# rgb.net
KiCad netlist of a schematic drawn in EAGLE
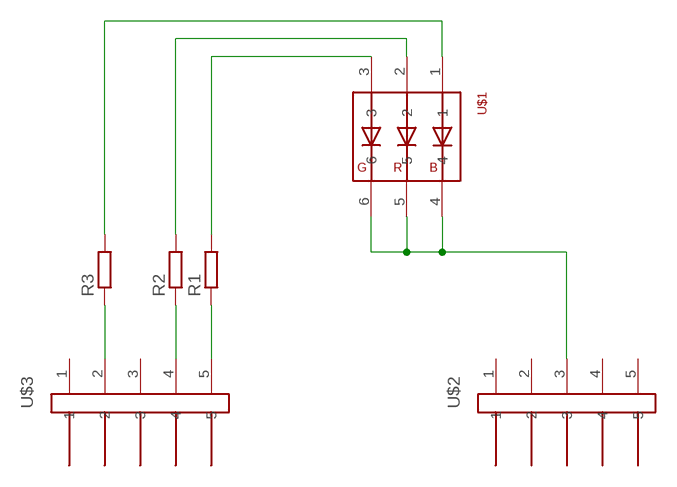
[diagram p0: schematic, sheet 1]

(export (version "E")
  (design (tool "Eeschema 10.0.6"))
  (components
    (comp (ref "R1")
      (value "R-EU_R0603")
      (footprint "eagle-import:R0603")
      (libsource (lib "eagle-import") (part "R-EU_R0603"))
    )
    (comp (ref "R2")
      (value "R-EU_R0603")
      (footprint "eagle-import:R0603")
      (libsource (lib "eagle-import") (part "R-EU_R0603"))
    )
    (comp (ref "R3")
      (value "R-EU_R0603")
      (footprint "eagle-import:R0603")
      (libsource (lib "eagle-import") (part "R-EU_R0603"))
    )
    (comp (ref "U$1")
      (value "RGB_WW-FCE50TC-Q1")
      (footprint "eagle-import:RGB_WW-FCE50TC-Q1")
      (libsource (lib "eagle-import") (part "RGB_WW-FCE50TC-Q1"))
    )
    (comp (ref "U$2")
      (value "JUMPER5M")
      (footprint "eagle-import:JUMPER5M")
      (libsource (lib "eagle-import") (part "JUMPER5M"))
    )
    (comp (ref "U$3")
      (value "JUMPER5M")
      (footprint "eagle-import:JUMPER5M")
      (libsource (lib "eagle-import") (part "JUMPER5M"))
    )
  )
  (nets
    (net (code "1") (name "Net-(R1-Pad1)") (class "Default")
      (node (ref "R1") (pin "1") (pinfunction "1_1") (pintype "passive"))
      (node (ref "U$3") (pin "5") (pinfunction "5_5") (pintype "bidirectional"))
    )
    (net (code "2") (name "Net-(R1-Pad2)") (class "Default")
      (node (ref "R1") (pin "2") (pinfunction "2_2") (pintype "passive"))
      (node (ref "U$1") (pin "3") (pinfunction "3_3") (pintype "bidirectional"))
    )
    (net (code "3") (name "Net-(R2-Pad1)") (class "Default")
      (node (ref "R2") (pin "1") (pinfunction "1_1") (pintype "passive"))
      (node (ref "U$3") (pin "4") (pinfunction "4_4") (pintype "bidirectional"))
    )
    (net (code "4") (name "Net-(R2-Pad2)") (class "Default")
      (node (ref "R2") (pin "2") (pinfunction "2_2") (pintype "passive"))
      (node (ref "U$1") (pin "2") (pinfunction "2_2") (pintype "bidirectional"))
    )
    (net (code "5") (name "Net-(R3-Pad1)") (class "Default")
      (node (ref "R3") (pin "1") (pinfunction "1_1") (pintype "passive"))
      (node (ref "U$3") (pin "2") (pinfunction "2_2") (pintype "bidirectional"))
    )
    (net (code "6") (name "Net-(R3-Pad2)") (class "Default")
      (node (ref "R3") (pin "2") (pinfunction "2_2") (pintype "passive"))
      (node (ref "U$1") (pin "1") (pinfunction "1_1") (pintype "bidirectional"))
    )
    (net (code "7") (name "Net-(U$1-Pad4)") (class "Default")
      (node (ref "U$1") (pin "4") (pinfunction "4_4") (pintype "bidirectional"))
      (node (ref "U$1") (pin "5") (pinfunction "5_5") (pintype "bidirectional"))
      (node (ref "U$1") (pin "6") (pinfunction "6_6") (pintype "bidirectional"))
      (node (ref "U$2") (pin "3") (pinfunction "3_3") (pintype "bidirectional"))
    )
    (net (code "8") (name "unconnected-(U$2-Pad1)") (class "Default")
      (node (ref "U$2") (pin "1") (pinfunction "1_1") (pintype "bidirectional"))
    )
    (net (code "9") (name "unconnected-(U$2-Pad2)") (class "Default")
      (node (ref "U$2") (pin "2") (pinfunction "2_2") (pintype "bidirectional"))
    )
    (net (code "10") (name "unconnected-(U$2-Pad4)") (class "Default")
      (node (ref "U$2") (pin "4") (pinfunction "4_4") (pintype "bidirectional"))
    )
    (net (code "11") (name "unconnected-(U$2-Pad5)") (class "Default")
      (node (ref "U$2") (pin "5") (pinfunction "5_5") (pintype "bidirectional"))
    )
    (net (code "12") (name "unconnected-(U$3-Pad1)") (class "Default")
      (node (ref "U$3") (pin "1") (pinfunction "1_1") (pintype "bidirectional"))
    )
    (net (code "13") (name "unconnected-(U$3-Pad3)") (class "Default")
      (node (ref "U$3") (pin "3") (pinfunction "3_3") (pintype "bidirectional"))
    )
  )
)
